# Shematic.net
KiCad netlist of a schematic drawn in EAGLE
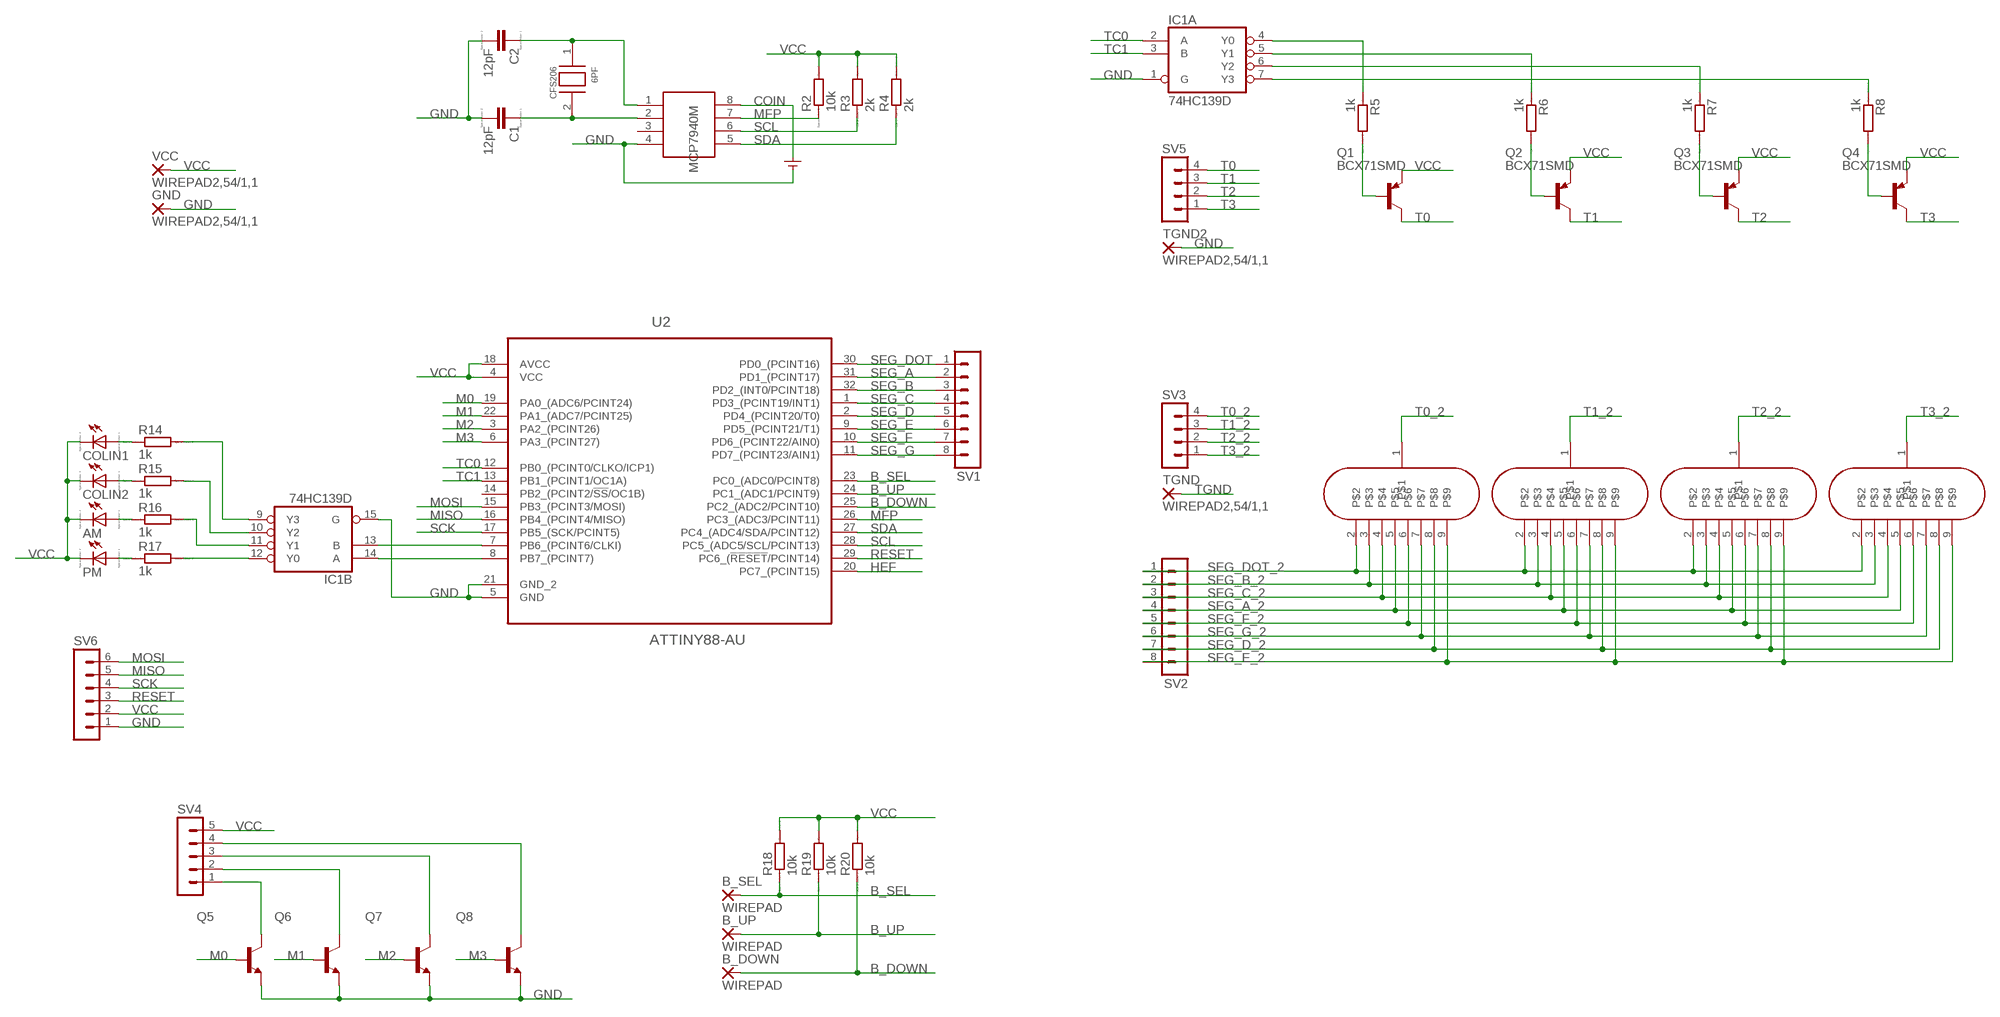
[diagram p0: schematic, sheet 1]

(export (version "E")
  (design (tool "Eeschema 10.0.6"))
  (components
    (comp (ref "6PF")
      (value "CFS206")
      (footprint "eagle-import:CFS206")
      (libsource (lib "eagle-import") (part "CFS206"))
    )
    (comp (ref "AM")
      (value "LED_ELD260")
      (footprint "eagle-import:LED_LD260")
      (libsource (lib "eagle-import") (part "LED_ELD260"))
    )
    (comp (ref "B_DOWN")
      (value "WIREPAD")
      (footprint "eagle-import:2,54_1,1")
      (libsource (lib "eagle-import") (part "WIREPAD2,54/1,1"))
    )
    (comp (ref "B_SEL")
      (value "WIREPAD")
      (footprint "eagle-import:2,54_1,1")
      (libsource (lib "eagle-import") (part "WIREPAD2,54/1,1"))
    )
    (comp (ref "B_UP")
      (value "WIREPAD")
      (footprint "eagle-import:2,54_1,1")
      (libsource (lib "eagle-import") (part "WIREPAD2,54/1,1"))
    )
    (comp (ref "C1")
      (value "12pF")
      (footprint "eagle-import:C1206")
      (libsource (lib "eagle-import") (part "CC1206"))
    )
    (comp (ref "C2")
      (value "12pF")
      (footprint "eagle-import:C1206")
      (libsource (lib "eagle-import") (part "CC1206"))
    )
    (comp (ref "COLIN1")
      (value "LED_ELD260")
      (footprint "eagle-import:LED_LD260")
      (libsource (lib "eagle-import") (part "LED_ELD260"))
    )
    (comp (ref "COLIN2")
      (value "LED_ELD260")
      (footprint "eagle-import:LED_LD260")
      (libsource (lib "eagle-import") (part "LED_ELD260"))
    )
    (comp (ref "GND")
      (value "WIREPAD2,54/1,1")
      (footprint "eagle-import:2,54_1,1")
      (libsource (lib "eagle-import") (part "WIREPAD2,54/1,1"))
    )
    (comp (ref "IC1")
      (value "74HC139D")
      (footprint "eagle-import:SO16")
      (libsource (lib "eagle-import") (part "74139DHC"))
    )
    (comp (ref "MCP7940M")
      (value "SOIC-8")
      (footprint "eagle-import:SOIC-8")
      (libsource (lib "eagle-import") (part "SOIC-8"))
    )
    (comp (ref "PM")
      (value "LED_ELD260")
      (footprint "eagle-import:LED_LD260")
      (libsource (lib "eagle-import") (part "LED_ELD260"))
    )
    (comp (ref "Q1")
      (value "BCX71SMD")
      (footprint "eagle-import:SOT23")
      (libsource (lib "eagle-import") (part "BCX71SMD"))
    )
    (comp (ref "Q2")
      (value "BCX71SMD")
      (footprint "eagle-import:SOT23")
      (libsource (lib "eagle-import") (part "BCX71SMD"))
    )
    (comp (ref "Q3")
      (value "BCX71SMD")
      (footprint "eagle-import:SOT23")
      (libsource (lib "eagle-import") (part "BCX71SMD"))
    )
    (comp (ref "Q4")
      (value "BCX71SMD")
      (footprint "eagle-import:SOT23")
      (libsource (lib "eagle-import") (part "BCX71SMD"))
    )
    (comp (ref "Q5")
      (value "BCX70SMD")
      (footprint "eagle-import:SOT23")
      (libsource (lib "eagle-import") (part "BCX70SMD"))
    )
    (comp (ref "Q6")
      (value "BCX70SMD")
      (footprint "eagle-import:SOT23")
      (libsource (lib "eagle-import") (part "BCX70SMD"))
    )
    (comp (ref "Q7")
      (value "BCX70SMD")
      (footprint "eagle-import:SOT23")
      (libsource (lib "eagle-import") (part "BCX70SMD"))
    )
    (comp (ref "Q8")
      (value "BCX70SMD")
      (footprint "eagle-import:SOT23")
      (libsource (lib "eagle-import") (part "BCX70SMD"))
    )
    (comp (ref "R2")
      (value "10k")
      (footprint "eagle-import:R1206")
      (libsource (lib "eagle-import") (part "RR1206"))
    )
    (comp (ref "R3")
      (value "2k")
      (footprint "eagle-import:R1206")
      (libsource (lib "eagle-import") (part "RR1206"))
    )
    (comp (ref "R4")
      (value "2k")
      (footprint "eagle-import:R1206")
      (libsource (lib "eagle-import") (part "RR1206"))
    )
    (comp (ref "R5")
      (value "1k")
      (footprint "eagle-import:R1206")
      (libsource (lib "eagle-import") (part "RR1206"))
    )
    (comp (ref "R6")
      (value "1k")
      (footprint "eagle-import:R1206")
      (libsource (lib "eagle-import") (part "RR1206"))
    )
    (comp (ref "R7")
      (value "1k")
      (footprint "eagle-import:R1206")
      (libsource (lib "eagle-import") (part "RR1206"))
    )
    (comp (ref "R8")
      (value "1k")
      (footprint "eagle-import:R1206")
      (libsource (lib "eagle-import") (part "RR1206"))
    )
    (comp (ref "R14")
      (value "1k")
      (footprint "eagle-import:R1206")
      (libsource (lib "eagle-import") (part "RR1206"))
    )
    (comp (ref "R15")
      (value "1k")
      (footprint "eagle-import:R1206")
      (libsource (lib "eagle-import") (part "RR1206"))
    )
    (comp (ref "R16")
      (value "1k")
      (footprint "eagle-import:R1206")
      (libsource (lib "eagle-import") (part "RR1206"))
    )
    (comp (ref "R17")
      (value "1k")
      (footprint "eagle-import:R1206")
      (libsource (lib "eagle-import") (part "RR1206"))
    )
    (comp (ref "R18")
      (value "10k")
      (footprint "eagle-import:R1206")
      (libsource (lib "eagle-import") (part "RR1206"))
    )
    (comp (ref "R19")
      (value "10k")
      (footprint "eagle-import:R1206")
      (libsource (lib "eagle-import") (part "RR1206"))
    )
    (comp (ref "R20")
      (value "10k")
      (footprint "eagle-import:R1206")
      (libsource (lib "eagle-import") (part "RR1206"))
    )
    (comp (ref "SV1")
      (value "MA08-1")
      (footprint "eagle-import:MA08-1")
      (libsource (lib "eagle-import") (part "MA08-1"))
    )
    (comp (ref "SV2")
      (value "MA08-1")
      (footprint "eagle-import:MA08-1")
      (libsource (lib "eagle-import") (part "MA08-1"))
    )
    (comp (ref "SV3")
      (value "MA04-1")
      (footprint "eagle-import:MA04-1")
      (libsource (lib "eagle-import") (part "MA04-1"))
    )
    (comp (ref "SV4")
      (value "MA05-1")
      (footprint "eagle-import:MA05-1")
      (libsource (lib "eagle-import") (part "MA05-1"))
    )
    (comp (ref "SV5")
      (value "MA04-1")
      (footprint "eagle-import:MA04-1")
      (libsource (lib "eagle-import") (part "MA04-1"))
    )
    (comp (ref "SV6")
      (value "MA06-1")
      (footprint "eagle-import:MA06-1")
      (libsource (lib "eagle-import") (part "MA06-1"))
    )
    (comp (ref "TGND")
      (value "WIREPAD2,54/1,1")
      (footprint "eagle-import:2,54_1,1")
      (libsource (lib "eagle-import") (part "WIREPAD2,54/1,1"))
    )
    (comp (ref "TGND2")
      (value "WIREPAD2,54/1,1")
      (footprint "eagle-import:2,54_1,1")
      (libsource (lib "eagle-import") (part "WIREPAD2,54/1,1"))
    )
    (comp (ref "TUBE0")
      (value "IV-9")
      (footprint "eagle-import:IV-9")
      (libsource (lib "eagle-import") (part "IV-9"))
    )
    (comp (ref "TUBE1")
      (value "IV-9")
      (footprint "eagle-import:IV-9")
      (libsource (lib "eagle-import") (part "IV-9"))
    )
    (comp (ref "TUBE2")
      (value "IV-9")
      (footprint "eagle-import:IV-9")
      (libsource (lib "eagle-import") (part "IV-9"))
    )
    (comp (ref "TUBE3")
      (value "IV-9")
      (footprint "eagle-import:IV-9")
      (libsource (lib "eagle-import") (part "IV-9"))
    )
    (comp (ref "U$5")
      (value "COIN")
      (footprint "eagle-import:COIN")
      (libsource (lib "eagle-import") (part "COIN"))
    )
    (comp (ref "U2")
      (value "ATTINY88-AU")
      (footprint "eagle-import:QFP80P900X900X120-32N")
      (libsource (lib "eagle-import") (part "ATTINY88-AU"))
    )
    (comp (ref "VCC")
      (value "WIREPAD2,54/1,1")
      (footprint "eagle-import:2,54_1,1")
      (libsource (lib "eagle-import") (part "WIREPAD2,54/1,1"))
    )
  )
  (nets
    (net (code "1") (name "/B_DOWN") (class "Default")
      (node (ref "B_DOWN") (pin "1") (pinfunction "P_1") (pintype "passive"))
      (node (ref "R20") (pin "1") (pinfunction "1_1") (pintype "passive"))
      (node (ref "U2") (pin "25") (pinfunction "PC2_(ADC2/PCINT10)_25") (pintype "bidirectional"))
    )
    (net (code "2") (name "/B_SEL") (class "Default")
      (node (ref "B_SEL") (pin "1") (pinfunction "P_1") (pintype "passive"))
      (node (ref "R18") (pin "1") (pinfunction "1_1") (pintype "passive"))
      (node (ref "U2") (pin "23") (pinfunction "PC0_(ADC0/PCINT8)_23") (pintype "bidirectional"))
    )
    (net (code "3") (name "/B_UP") (class "Default")
      (node (ref "B_UP") (pin "1") (pinfunction "P_1") (pintype "passive"))
      (node (ref "R19") (pin "1") (pinfunction "1_1") (pintype "passive"))
      (node (ref "U2") (pin "24") (pinfunction "PC1_(ADC1/PCINT9)_24") (pintype "bidirectional"))
    )
    (net (code "4") (name "/COIN") (class "Default")
      (node (ref "MCP7940M") (pin "8") (pinfunction "P$8_8") (pintype "bidirectional"))
      (node (ref "U$5") (pin "V+") (pinfunction "V+_V+") (pintype "bidirectional"))
    )
    (net (code "5") (name "/GND") (class "Default")
      (node (ref "C1") (pin "2") (pinfunction "2_2") (pintype "passive"))
      (node (ref "C2") (pin "2") (pinfunction "2_2") (pintype "passive"))
      (node (ref "GND") (pin "1") (pinfunction "P_1") (pintype "passive"))
      (node (ref "IC1") (pin "1") (pinfunction "G_1") (pintype "input"))
      (node (ref "IC1") (pin "15") (pinfunction "G_15") (pintype "input"))
      (node (ref "MCP7940M") (pin "4") (pinfunction "P$4_4") (pintype "bidirectional"))
      (node (ref "Q5") (pin "2") (pinfunction "E_2") (pintype "passive"))
      (node (ref "Q6") (pin "2") (pinfunction "E_2") (pintype "passive"))
      (node (ref "Q7") (pin "2") (pinfunction "E_2") (pintype "passive"))
      (node (ref "Q8") (pin "2") (pinfunction "E_2") (pintype "passive"))
      (node (ref "SV6") (pin "1") (pinfunction "1_1") (pintype "passive"))
      (node (ref "TGND2") (pin "1") (pinfunction "P_1") (pintype "passive"))
      (node (ref "U$5") (pin "V-") (pinfunction "V-_V-") (pintype "bidirectional"))
      (node (ref "U2") (pin "21") (pinfunction "GND_2_21") (pintype "passive"))
      (node (ref "U2") (pin "5") (pinfunction "GND_5") (pintype "passive"))
    )
    (net (code "6") (name "/HEF") (class "Default")
      (node (ref "U2") (pin "20") (pinfunction "PC7_(PCINT15)_20") (pintype "bidirectional"))
    )
    (net (code "7") (name "/M0") (class "Default")
      (node (ref "Q5") (pin "1") (pinfunction "B_1") (pintype "passive"))
      (node (ref "U2") (pin "19") (pinfunction "PA0_(ADC6/PCINT24)_19") (pintype "bidirectional"))
    )
    (net (code "8") (name "/M1") (class "Default")
      (node (ref "Q6") (pin "1") (pinfunction "B_1") (pintype "passive"))
      (node (ref "U2") (pin "22") (pinfunction "PA1_(ADC7/PCINT25)_22") (pintype "bidirectional"))
    )
    (net (code "9") (name "/M2") (class "Default")
      (node (ref "Q7") (pin "1") (pinfunction "B_1") (pintype "passive"))
      (node (ref "U2") (pin "3") (pinfunction "PA2_(PCINT26)_3") (pintype "bidirectional"))
    )
    (net (code "10") (name "/M3") (class "Default")
      (node (ref "Q8") (pin "1") (pinfunction "B_1") (pintype "passive"))
      (node (ref "U2") (pin "6") (pinfunction "PA3_(PCINT27)_6") (pintype "bidirectional"))
    )
    (net (code "11") (name "/MFP") (class "Default")
      (node (ref "MCP7940M") (pin "7") (pinfunction "P$7_7") (pintype "bidirectional"))
      (node (ref "R2") (pin "1") (pinfunction "1_1") (pintype "passive"))
      (node (ref "U2") (pin "26") (pinfunction "PC3_(ADC3/PCINT11)_26") (pintype "bidirectional"))
    )
    (net (code "12") (name "/MISO") (class "Default")
      (node (ref "SV6") (pin "5") (pinfunction "5_5") (pintype "passive"))
      (node (ref "U2") (pin "16") (pinfunction "PB4_(PCINT4/MISO)_16") (pintype "bidirectional"))
    )
    (net (code "13") (name "/MOSI") (class "Default")
      (node (ref "SV6") (pin "6") (pinfunction "6_6") (pintype "passive"))
      (node (ref "U2") (pin "15") (pinfunction "PB3_(PCINT3/MOSI)_15") (pintype "bidirectional"))
    )
    (net (code "14") (name "/RESET") (class "Default")
      (node (ref "SV6") (pin "3") (pinfunction "3_3") (pintype "passive"))
      (node (ref "U2") (pin "29") (pinfunction "PC6_(~{RESET}/PCINT14)_29") (pintype "bidirectional"))
    )
    (net (code "15") (name "/SCK") (class "Default")
      (node (ref "SV6") (pin "4") (pinfunction "4_4") (pintype "passive"))
      (node (ref "U2") (pin "17") (pinfunction "PB5_(SCK/PCINT5)_17") (pintype "bidirectional"))
    )
    (net (code "16") (name "/SCL") (class "Default")
      (node (ref "MCP7940M") (pin "6") (pinfunction "P$6_6") (pintype "bidirectional"))
      (node (ref "R3") (pin "1") (pinfunction "1_1") (pintype "passive"))
      (node (ref "U2") (pin "28") (pinfunction "PC5_(ADC5/SCL/PCINT13)_28") (pintype "bidirectional"))
    )
    (net (code "17") (name "/SDA") (class "Default")
      (node (ref "MCP7940M") (pin "5") (pinfunction "P$5_5") (pintype "bidirectional"))
      (node (ref "R4") (pin "1") (pinfunction "1_1") (pintype "passive"))
      (node (ref "U2") (pin "27") (pinfunction "PC4_(ADC4/SDA/PCINT12)_27") (pintype "bidirectional"))
    )
    (net (code "18") (name "/SEG_A") (class "Default")
      (node (ref "SV1") (pin "2") (pinfunction "2_2") (pintype "passive"))
      (node (ref "U2") (pin "31") (pinfunction "PD1_(PCINT17)_31") (pintype "bidirectional"))
    )
    (net (code "19") (name "/SEG_A_2") (class "Default")
      (node (ref "SV2") (pin "4") (pinfunction "4_4") (pintype "passive"))
      (node (ref "TUBE0") (pin "5") (pinfunction "P$5_5") (pintype "bidirectional"))
      (node (ref "TUBE1") (pin "5") (pinfunction "P$5_5") (pintype "bidirectional"))
      (node (ref "TUBE2") (pin "5") (pinfunction "P$5_5") (pintype "bidirectional"))
      (node (ref "TUBE3") (pin "5") (pinfunction "P$5_5") (pintype "bidirectional"))
    )
    (net (code "20") (name "/SEG_B") (class "Default")
      (node (ref "SV1") (pin "3") (pinfunction "3_3") (pintype "passive"))
      (node (ref "U2") (pin "32") (pinfunction "PD2_(INT0/PCINT18)_32") (pintype "bidirectional"))
    )
    (net (code "21") (name "/SEG_B_2") (class "Default")
      (node (ref "SV2") (pin "2") (pinfunction "2_2") (pintype "passive"))
      (node (ref "TUBE0") (pin "3") (pinfunction "P$3_3") (pintype "bidirectional"))
      (node (ref "TUBE1") (pin "3") (pinfunction "P$3_3") (pintype "bidirectional"))
      (node (ref "TUBE2") (pin "3") (pinfunction "P$3_3") (pintype "bidirectional"))
      (node (ref "TUBE3") (pin "3") (pinfunction "P$3_3") (pintype "bidirectional"))
    )
    (net (code "22") (name "/SEG_C") (class "Default")
      (node (ref "SV1") (pin "4") (pinfunction "4_4") (pintype "passive"))
      (node (ref "U2") (pin "1") (pinfunction "PD3_(PCINT19/INT1)_1") (pintype "bidirectional"))
    )
    (net (code "23") (name "/SEG_C_2") (class "Default")
      (node (ref "SV2") (pin "3") (pinfunction "3_3") (pintype "passive"))
      (node (ref "TUBE0") (pin "4") (pinfunction "P$4_4") (pintype "bidirectional"))
      (node (ref "TUBE1") (pin "4") (pinfunction "P$4_4") (pintype "bidirectional"))
      (node (ref "TUBE2") (pin "4") (pinfunction "P$4_4") (pintype "bidirectional"))
      (node (ref "TUBE3") (pin "4") (pinfunction "P$4_4") (pintype "bidirectional"))
    )
    (net (code "24") (name "/SEG_D") (class "Default")
      (node (ref "SV1") (pin "5") (pinfunction "5_5") (pintype "passive"))
      (node (ref "U2") (pin "2") (pinfunction "PD4_(PCINT20/T0)_2") (pintype "bidirectional"))
    )
    (net (code "25") (name "/SEG_DOT") (class "Default")
      (node (ref "SV1") (pin "1") (pinfunction "1_1") (pintype "passive"))
      (node (ref "U2") (pin "30") (pinfunction "PD0_(PCINT16)_30") (pintype "bidirectional"))
    )
    (net (code "26") (name "/SEG_DOT_2") (class "Default")
      (node (ref "SV2") (pin "1") (pinfunction "1_1") (pintype "passive"))
      (node (ref "TUBE0") (pin "2") (pinfunction "P$2_2") (pintype "bidirectional"))
      (node (ref "TUBE1") (pin "2") (pinfunction "P$2_2") (pintype "bidirectional"))
      (node (ref "TUBE2") (pin "2") (pinfunction "P$2_2") (pintype "bidirectional"))
      (node (ref "TUBE3") (pin "2") (pinfunction "P$2_2") (pintype "bidirectional"))
    )
    (net (code "27") (name "/SEG_D_2") (class "Default")
      (node (ref "SV2") (pin "7") (pinfunction "7_7") (pintype "passive"))
      (node (ref "TUBE0") (pin "8") (pinfunction "P$8_8") (pintype "bidirectional"))
      (node (ref "TUBE1") (pin "8") (pinfunction "P$8_8") (pintype "bidirectional"))
      (node (ref "TUBE2") (pin "8") (pinfunction "P$8_8") (pintype "bidirectional"))
      (node (ref "TUBE3") (pin "8") (pinfunction "P$8_8") (pintype "bidirectional"))
    )
    (net (code "28") (name "/SEG_E") (class "Default")
      (node (ref "SV1") (pin "6") (pinfunction "6_6") (pintype "passive"))
      (node (ref "U2") (pin "9") (pinfunction "PD5_(PCINT21/T1)_9") (pintype "bidirectional"))
    )
    (net (code "29") (name "/SEG_E_2") (class "Default")
      (node (ref "SV2") (pin "8") (pinfunction "8_8") (pintype "passive"))
      (node (ref "TUBE0") (pin "9") (pinfunction "P$9_9") (pintype "bidirectional"))
      (node (ref "TUBE1") (pin "9") (pinfunction "P$9_9") (pintype "bidirectional"))
      (node (ref "TUBE2") (pin "9") (pinfunction "P$9_9") (pintype "bidirectional"))
      (node (ref "TUBE3") (pin "9") (pinfunction "P$9_9") (pintype "bidirectional"))
    )
    (net (code "30") (name "/SEG_F") (class "Default")
      (node (ref "SV1") (pin "7") (pinfunction "7_7") (pintype "passive"))
      (node (ref "U2") (pin "10") (pinfunction "PD6_(PCINT22/AIN0)_10") (pintype "bidirectional"))
    )
    (net (code "31") (name "/SEG_F_2") (class "Default")
      (node (ref "SV2") (pin "5") (pinfunction "5_5") (pintype "passive"))
      (node (ref "TUBE0") (pin "6") (pinfunction "P$6_6") (pintype "bidirectional"))
      (node (ref "TUBE1") (pin "6") (pinfunction "P$6_6") (pintype "bidirectional"))
      (node (ref "TUBE2") (pin "6") (pinfunction "P$6_6") (pintype "bidirectional"))
      (node (ref "TUBE3") (pin "6") (pinfunction "P$6_6") (pintype "bidirectional"))
    )
    (net (code "32") (name "/SEG_G") (class "Default")
      (node (ref "SV1") (pin "8") (pinfunction "8_8") (pintype "passive"))
      (node (ref "U2") (pin "11") (pinfunction "PD7_(PCINT23/AIN1)_11") (pintype "bidirectional"))
    )
    (net (code "33") (name "/SEG_G_2") (class "Default")
      (node (ref "SV2") (pin "6") (pinfunction "6_6") (pintype "passive"))
      (node (ref "TUBE0") (pin "7") (pinfunction "P$7_7") (pintype "bidirectional"))
      (node (ref "TUBE1") (pin "7") (pinfunction "P$7_7") (pintype "bidirectional"))
      (node (ref "TUBE2") (pin "7") (pinfunction "P$7_7") (pintype "bidirectional"))
      (node (ref "TUBE3") (pin "7") (pinfunction "P$7_7") (pintype "bidirectional"))
    )
    (net (code "34") (name "/T0") (class "Default")
      (node (ref "Q1") (pin "3") (pinfunction "C_3") (pintype "passive"))
      (node (ref "SV5") (pin "4") (pinfunction "4_4") (pintype "passive"))
    )
    (net (code "35") (name "/T0_2") (class "Default")
      (node (ref "SV3") (pin "4") (pinfunction "4_4") (pintype "passive"))
      (node (ref "TUBE0") (pin "1") (pinfunction "P$1_1") (pintype "bidirectional"))
    )
    (net (code "36") (name "/T1") (class "Default")
      (node (ref "Q2") (pin "3") (pinfunction "C_3") (pintype "passive"))
      (node (ref "SV5") (pin "3") (pinfunction "3_3") (pintype "passive"))
    )
    (net (code "37") (name "/T1_2") (class "Default")
      (node (ref "SV3") (pin "3") (pinfunction "3_3") (pintype "passive"))
      (node (ref "TUBE1") (pin "1") (pinfunction "P$1_1") (pintype "bidirectional"))
    )
    (net (code "38") (name "/T2") (class "Default")
      (node (ref "Q3") (pin "3") (pinfunction "C_3") (pintype "passive"))
      (node (ref "SV5") (pin "2") (pinfunction "2_2") (pintype "passive"))
    )
    (net (code "39") (name "/T2_2") (class "Default")
      (node (ref "SV3") (pin "2") (pinfunction "2_2") (pintype "passive"))
      (node (ref "TUBE2") (pin "1") (pinfunction "P$1_1") (pintype "bidirectional"))
    )
    (net (code "40") (name "/T3") (class "Default")
      (node (ref "Q4") (pin "3") (pinfunction "C_3") (pintype "passive"))
      (node (ref "SV5") (pin "1") (pinfunction "1_1") (pintype "passive"))
    )
    (net (code "41") (name "/T3_2") (class "Default")
      (node (ref "SV3") (pin "1") (pinfunction "1_1") (pintype "passive"))
      (node (ref "TUBE3") (pin "1") (pinfunction "P$1_1") (pintype "bidirectional"))
    )
    (net (code "42") (name "/TC0") (class "Default")
      (node (ref "IC1") (pin "2") (pinfunction "A_2") (pintype "input"))
      (node (ref "U2") (pin "12") (pinfunction "PB0_(PCINT0/CLKO/ICP1)_12") (pintype "bidirectional"))
    )
    (net (code "43") (name "/TC1") (class "Default")
      (node (ref "IC1") (pin "3") (pinfunction "B_3") (pintype "input"))
      (node (ref "U2") (pin "13") (pinfunction "PB1_(PCINT1/OC1A)_13") (pintype "bidirectional"))
    )
    (net (code "44") (name "/TGND") (class "Default")
      (node (ref "TGND") (pin "1") (pinfunction "P_1") (pintype "passive"))
    )
    (net (code "45") (name "/VCC") (class "Default")
      (node (ref "AM") (pin "K") (pinfunction "C_K") (pintype "passive"))
      (node (ref "COLIN1") (pin "K") (pinfunction "C_K") (pintype "passive"))
      (node (ref "COLIN2") (pin "K") (pinfunction "C_K") (pintype "passive"))
      (node (ref "PM") (pin "K") (pinfunction "C_K") (pintype "passive"))
      (node (ref "Q1") (pin "2") (pinfunction "E_2") (pintype "passive"))
      (node (ref "Q2") (pin "2") (pinfunction "E_2") (pintype "passive"))
      (node (ref "Q3") (pin "2") (pinfunction "E_2") (pintype "passive"))
      (node (ref "Q4") (pin "2") (pinfunction "E_2") (pintype "passive"))
      (node (ref "R18") (pin "2") (pinfunction "2_2") (pintype "passive"))
      (node (ref "R19") (pin "2") (pinfunction "2_2") (pintype "passive"))
      (node (ref "R2") (pin "2") (pinfunction "2_2") (pintype "passive"))
      (node (ref "R20") (pin "2") (pinfunction "2_2") (pintype "passive"))
      (node (ref "R3") (pin "2") (pinfunction "2_2") (pintype "passive"))
      (node (ref "R4") (pin "2") (pinfunction "2_2") (pintype "passive"))
      (node (ref "SV4") (pin "5") (pinfunction "5_5") (pintype "passive"))
      (node (ref "SV6") (pin "2") (pinfunction "2_2") (pintype "passive"))
      (node (ref "U2") (pin "18") (pinfunction "AVCC_18") (pintype "power_in"))
      (node (ref "U2") (pin "4") (pinfunction "VCC_4") (pintype "power_in"))
      (node (ref "VCC") (pin "1") (pinfunction "P_1") (pintype "passive"))
    )
    (net (code "46") (name "Net-(6PF-P$1)") (class "Default")
      (node (ref "6PF") (pin "1") (pinfunction "P$1_1") (pintype "bidirectional"))
      (node (ref "C2") (pin "1") (pinfunction "1_1") (pintype "passive"))
      (node (ref "MCP7940M") (pin "1") (pinfunction "P$1_1") (pintype "bidirectional"))
    )
    (net (code "47") (name "Net-(6PF-P$2)") (class "Default")
      (node (ref "6PF") (pin "2") (pinfunction "P$2_2") (pintype "bidirectional"))
      (node (ref "C1") (pin "1") (pinfunction "1_1") (pintype "passive"))
      (node (ref "MCP7940M") (pin "2") (pinfunction "P$2_2") (pintype "bidirectional"))
    )
    (net (code "48") (name "Net-(AM-PadA)") (class "Default")
      (node (ref "AM") (pin "A") (pinfunction "A_A") (pintype "passive"))
      (node (ref "R16") (pin "1") (pinfunction "1_1") (pintype "passive"))
    )
    (net (code "49") (name "Net-(COLIN1-PadA)") (class "Default")
      (node (ref "COLIN1") (pin "A") (pinfunction "A_A") (pintype "passive"))
      (node (ref "R14") (pin "1") (pinfunction "1_1") (pintype "passive"))
    )
    (net (code "50") (name "Net-(COLIN2-PadA)") (class "Default")
      (node (ref "COLIN2") (pin "A") (pinfunction "A_A") (pintype "passive"))
      (node (ref "R15") (pin "1") (pinfunction "1_1") (pintype "passive"))
    )
    (net (code "51") (name "Net-(IC1A-Y0)") (class "Default")
      (node (ref "IC1") (pin "4") (pinfunction "Y0_4") (pintype "output"))
      (node (ref "R5") (pin "1") (pinfunction "1_1") (pintype "passive"))
    )
    (net (code "52") (name "Net-(IC1A-Y1)") (class "Default")
      (node (ref "IC1") (pin "5") (pinfunction "Y1_5") (pintype "output"))
      (node (ref "R6") (pin "1") (pinfunction "1_1") (pintype "passive"))
    )
    (net (code "53") (name "Net-(IC1A-Y2)") (class "Default")
      (node (ref "IC1") (pin "6") (pinfunction "Y2_6") (pintype "output"))
      (node (ref "R7") (pin "1") (pinfunction "1_1") (pintype "passive"))
    )
    (net (code "54") (name "Net-(IC1A-Y3)") (class "Default")
      (node (ref "IC1") (pin "7") (pinfunction "Y3_7") (pintype "output"))
      (node (ref "R8") (pin "1") (pinfunction "1_1") (pintype "passive"))
    )
    (net (code "55") (name "Net-(IC1B-A)") (class "Default")
      (node (ref "IC1") (pin "14") (pinfunction "A_14") (pintype "input"))
      (node (ref "U2") (pin "8") (pinfunction "PB7_(PCINT7)_8") (pintype "bidirectional"))
    )
    (net (code "56") (name "Net-(IC1B-B)") (class "Default")
      (node (ref "IC1") (pin "13") (pinfunction "B_13") (pintype "input"))
      (node (ref "U2") (pin "7") (pinfunction "PB6_(PCINT6/CLKI)_7") (pintype "bidirectional"))
    )
    (net (code "57") (name "Net-(IC1B-Y0)") (class "Default")
      (node (ref "IC1") (pin "12") (pinfunction "Y0_12") (pintype "output"))
      (node (ref "R17") (pin "2") (pinfunction "2_2") (pintype "passive"))
    )
    (net (code "58") (name "Net-(IC1B-Y1)") (class "Default")
      (node (ref "IC1") (pin "11") (pinfunction "Y1_11") (pintype "output"))
      (node (ref "R16") (pin "2") (pinfunction "2_2") (pintype "passive"))
    )
    (net (code "59") (name "Net-(IC1B-Y2)") (class "Default")
      (node (ref "IC1") (pin "10") (pinfunction "Y2_10") (pintype "output"))
      (node (ref "R15") (pin "2") (pinfunction "2_2") (pintype "passive"))
    )
    (net (code "60") (name "Net-(IC1B-Y3)") (class "Default")
      (node (ref "IC1") (pin "9") (pinfunction "Y3_9") (pintype "output"))
      (node (ref "R14") (pin "2") (pinfunction "2_2") (pintype "passive"))
    )
    (net (code "61") (name "Net-(PM-PadA)") (class "Default")
      (node (ref "PM") (pin "A") (pinfunction "A_A") (pintype "passive"))
      (node (ref "R17") (pin "1") (pinfunction "1_1") (pintype "passive"))
    )
    (net (code "62") (name "Net-(Q1-B)") (class "Default")
      (node (ref "Q1") (pin "1") (pinfunction "B_1") (pintype "passive"))
      (node (ref "R5") (pin "2") (pinfunction "2_2") (pintype "passive"))
    )
    (net (code "63") (name "Net-(Q2-B)") (class "Default")
      (node (ref "Q2") (pin "1") (pinfunction "B_1") (pintype "passive"))
      (node (ref "R6") (pin "2") (pinfunction "2_2") (pintype "passive"))
    )
    (net (code "64") (name "Net-(Q3-B)") (class "Default")
      (node (ref "Q3") (pin "1") (pinfunction "B_1") (pintype "passive"))
      (node (ref "R7") (pin "2") (pinfunction "2_2") (pintype "passive"))
    )
    (net (code "65") (name "Net-(Q4-B)") (class "Default")
      (node (ref "Q4") (pin "1") (pinfunction "B_1") (pintype "passive"))
      (node (ref "R8") (pin "2") (pinfunction "2_2") (pintype "passive"))
    )
    (net (code "66") (name "Net-(Q5-C)") (class "Default")
      (node (ref "Q5") (pin "3") (pinfunction "C_3") (pintype "passive"))
      (node (ref "SV4") (pin "1") (pinfunction "1_1") (pintype "passive"))
    )
    (net (code "67") (name "Net-(Q6-C)") (class "Default")
      (node (ref "Q6") (pin "3") (pinfunction "C_3") (pintype "passive"))
      (node (ref "SV4") (pin "2") (pinfunction "2_2") (pintype "passive"))
    )
    (net (code "68") (name "Net-(Q7-C)") (class "Default")
      (node (ref "Q7") (pin "3") (pinfunction "C_3") (pintype "passive"))
      (node (ref "SV4") (pin "3") (pinfunction "3_3") (pintype "passive"))
    )
    (net (code "69") (name "Net-(Q8-C)") (class "Default")
      (node (ref "Q8") (pin "3") (pinfunction "C_3") (pintype "passive"))
      (node (ref "SV4") (pin "4") (pinfunction "4_4") (pintype "passive"))
    )
    (net (code "70") (name "unconnected-(MCP7940M-P$3-Pad3)") (class "Default")
      (node (ref "MCP7940M") (pin "3") (pinfunction "P$3_3") (pintype "bidirectional"))
    )
    (net (code "71") (name "unconnected-(U2-PB2_(PCINT2{slash}~{SS}{slash}OC1B)-Pad14)") (class "Default")
      (node (ref "U2") (pin "14") (pinfunction "PB2_(PCINT2/~{SS}/OC1B)_14") (pintype "bidirectional"))
    )
  )
)
